# Warmie_Helper_Board_V_9_5_GND_EN_3_3v.net
KiCad netlist of a schematic drawn in EAGLE
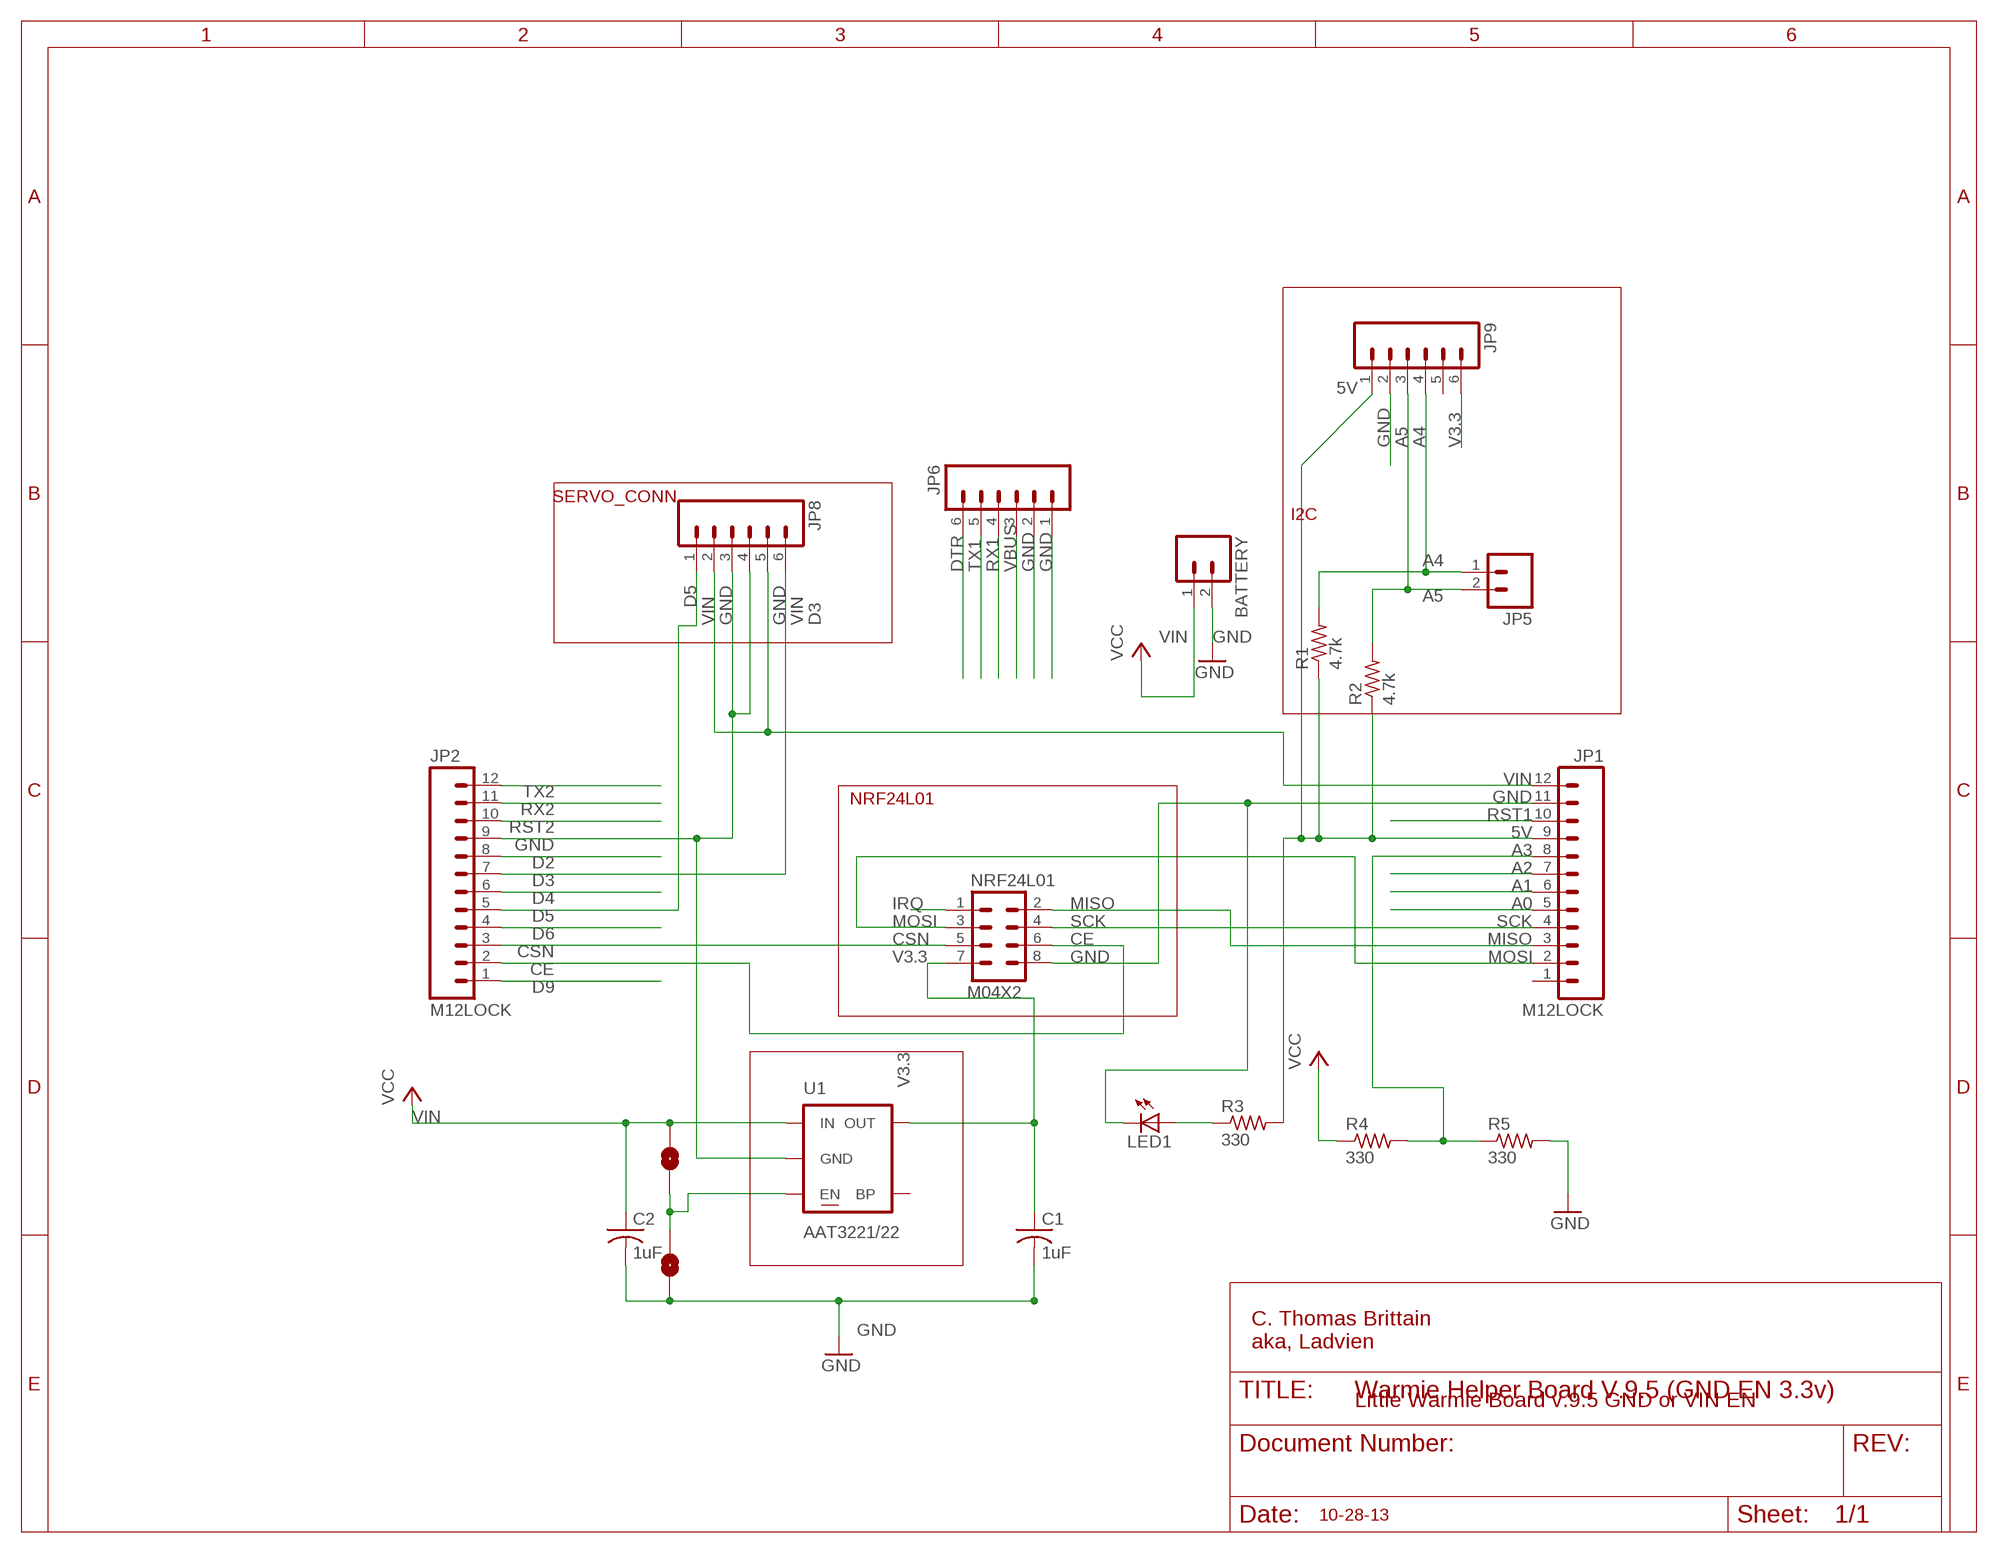
[diagram p0: schematic, sheet 1]

(export (version "E")
  (design (tool "Eeschema 10.0.6"))
  (components
    (comp (ref "BATTERY")
      (value "M02LOCK")
      (footprint "eagle-import:1X02_LOCK")
      (libsource (lib "eagle-import") (part "M02LOCK"))
    )
    (comp (ref "C1")
      (value "1uF")
      (footprint "eagle-import:C0805")
      (libsource (lib "eagle-import") (part "C-USC0805"))
    )
    (comp (ref "C2")
      (value "1uF")
      (footprint "eagle-import:C0805")
      (libsource (lib "eagle-import") (part "C-USC0805"))
    )
    (comp (ref "JP1")
      (value "M12LOCK")
      (footprint "eagle-import:1X12_LOCK")
      (libsource (lib "eagle-import") (part "M12LOCK"))
    )
    (comp (ref "JP2")
      (value "M12LOCK")
      (footprint "eagle-import:1X12_LOCK")
      (libsource (lib "eagle-import") (part "M12LOCK"))
    )
    (comp (ref "JP5")
      (value "M02LOCK")
      (footprint "eagle-import:1X02_LOCK")
      (libsource (lib "eagle-import") (part "M02LOCK"))
    )
    (comp (ref "JP6")
      (value "M06LOCK")
      (footprint "eagle-import:1X06_LOCK")
      (libsource (lib "eagle-import") (part "M06LOCK"))
    )
    (comp (ref "JP8")
      (value "M06LOCK")
      (footprint "eagle-import:1X06_LOCK")
      (libsource (lib "eagle-import") (part "M06LOCK"))
    )
    (comp (ref "JP9")
      (value "M06LOCK")
      (footprint "eagle-import:1X06_LOCK")
      (libsource (lib "eagle-import") (part "M06LOCK"))
    )
    (comp (ref "LED1")
      (value "LEDSML0603")
      (footprint "eagle-import:SML0603")
      (libsource (lib "eagle-import") (part "LEDSML0603"))
    )
    (comp (ref "NRF24L01")
      (value "M04X2")
      (footprint "eagle-import:2X4")
      (libsource (lib "eagle-import") (part "M04X2"))
    )
    (comp (ref "R1")
      (value "4.7k")
      (footprint "eagle-import:M0805")
      (libsource (lib "eagle-import") (part "R-US_M0805"))
    )
    (comp (ref "R2")
      (value "4.7k")
      (footprint "eagle-import:M0805")
      (libsource (lib "eagle-import") (part "R-US_M0805"))
    )
    (comp (ref "R3")
      (value "330")
      (footprint "eagle-import:M0805")
      (libsource (lib "eagle-import") (part "R-US_M0805"))
    )
    (comp (ref "R4")
      (value "330")
      (footprint "eagle-import:M0805")
      (libsource (lib "eagle-import") (part "R-US_M0805"))
    )
    (comp (ref "R5")
      (value "330")
      (footprint "eagle-import:M0805")
      (libsource (lib "eagle-import") (part "R-US_M0805"))
    )
    (comp (ref "SJ1")
      (value "SOLDERJUMPERNO")
      (footprint "eagle-import:SJ_2S-NO")
      (libsource (lib "eagle-import") (part "SOLDERJUMPERNO"))
    )
    (comp (ref "SJ2")
      (value "SOLDERJUMPERNO")
      (footprint "eagle-import:SJ_2S-NO")
      (libsource (lib "eagle-import") (part "SOLDERJUMPERNO"))
    )
    (comp (ref "U1")
      (value "AAT3221/22")
      (footprint "eagle-import:SOT23-5")
      (libsource (lib "eagle-import") (part "V_REG_LDOSMD"))
    )
  )
  (nets
    (net (code "1") (name "/5V") (class "Default")
      (node (ref "JP1") (pin "9") (pinfunction "9_9") (pintype "passive"))
      (node (ref "JP9") (pin "1") (pinfunction "1_1") (pintype "passive"))
      (node (ref "R1") (pin "1") (pinfunction "1_1") (pintype "passive"))
      (node (ref "R2") (pin "1") (pinfunction "1_1") (pintype "passive"))
      (node (ref "R3") (pin "2") (pinfunction "2_2") (pintype "passive"))
    )
    (net (code "2") (name "/A0") (class "Default")
      (node (ref "JP1") (pin "5") (pinfunction "5_5") (pintype "passive"))
    )
    (net (code "3") (name "/A1") (class "Default")
      (node (ref "JP1") (pin "6") (pinfunction "6_6") (pintype "passive"))
    )
    (net (code "4") (name "/A2") (class "Default")
      (node (ref "JP1") (pin "7") (pinfunction "7_7") (pintype "passive"))
    )
    (net (code "5") (name "/A3") (class "Default")
      (node (ref "JP1") (pin "8") (pinfunction "8_8") (pintype "passive"))
      (node (ref "R4") (pin "2") (pinfunction "2_2") (pintype "passive"))
      (node (ref "R5") (pin "1") (pinfunction "1_1") (pintype "passive"))
    )
    (net (code "6") (name "/A4") (class "Default")
      (node (ref "JP5") (pin "1") (pinfunction "1_1") (pintype "passive"))
      (node (ref "JP9") (pin "4") (pinfunction "4_4") (pintype "passive"))
      (node (ref "R1") (pin "2") (pinfunction "2_2") (pintype "passive"))
    )
    (net (code "7") (name "/A5") (class "Default")
      (node (ref "JP5") (pin "2") (pinfunction "2_2") (pintype "passive"))
      (node (ref "JP9") (pin "3") (pinfunction "3_3") (pintype "passive"))
      (node (ref "R2") (pin "2") (pinfunction "2_2") (pintype "passive"))
    )
    (net (code "8") (name "/CE") (class "Default")
      (node (ref "JP2") (pin "2") (pinfunction "2_2") (pintype "passive"))
      (node (ref "NRF24L01") (pin "6") (pinfunction "6_6") (pintype "passive"))
    )
    (net (code "9") (name "/CSN") (class "Default")
      (node (ref "JP2") (pin "3") (pinfunction "3_3") (pintype "passive"))
      (node (ref "NRF24L01") (pin "5") (pinfunction "5_5") (pintype "passive"))
    )
    (net (code "10") (name "/D2") (class "Default")
      (node (ref "JP2") (pin "8") (pinfunction "8_8") (pintype "passive"))
    )
    (net (code "11") (name "/D3") (class "Default")
      (node (ref "JP2") (pin "7") (pinfunction "7_7") (pintype "passive"))
      (node (ref "JP8") (pin "6") (pinfunction "6_6") (pintype "passive"))
    )
    (net (code "12") (name "/D4") (class "Default")
      (node (ref "JP2") (pin "6") (pinfunction "6_6") (pintype "passive"))
    )
    (net (code "13") (name "/D5") (class "Default")
      (node (ref "JP2") (pin "5") (pinfunction "5_5") (pintype "passive"))
      (node (ref "JP8") (pin "1") (pinfunction "1_1") (pintype "passive"))
    )
    (net (code "14") (name "/D6") (class "Default")
      (node (ref "JP2") (pin "4") (pinfunction "4_4") (pintype "passive"))
    )
    (net (code "15") (name "/D9") (class "Default")
      (node (ref "JP2") (pin "1") (pinfunction "1_1") (pintype "passive"))
    )
    (net (code "16") (name "/DTR") (class "Default")
      (node (ref "JP6") (pin "6") (pinfunction "6_6") (pintype "passive"))
    )
    (net (code "17") (name "/IRQ") (class "Default")
      (node (ref "NRF24L01") (pin "1") (pinfunction "1_1") (pintype "passive"))
    )
    (net (code "18") (name "/MISO") (class "Default")
      (node (ref "JP1") (pin "3") (pinfunction "3_3") (pintype "passive"))
      (node (ref "NRF24L01") (pin "2") (pinfunction "2_2") (pintype "passive"))
    )
    (net (code "19") (name "/MOSI") (class "Default")
      (node (ref "JP1") (pin "2") (pinfunction "2_2") (pintype "passive"))
      (node (ref "NRF24L01") (pin "3") (pinfunction "3_3") (pintype "passive"))
    )
    (net (code "20") (name "/RST1") (class "Default")
      (node (ref "JP1") (pin "10") (pinfunction "10_10") (pintype "passive"))
    )
    (net (code "21") (name "/RST2") (class "Default")
      (node (ref "JP2") (pin "10") (pinfunction "10_10") (pintype "passive"))
    )
    (net (code "22") (name "/RX1") (class "Default")
      (node (ref "JP6") (pin "4") (pinfunction "4_4") (pintype "passive"))
    )
    (net (code "23") (name "/RX2") (class "Default")
      (node (ref "JP2") (pin "11") (pinfunction "11_11") (pintype "passive"))
    )
    (net (code "24") (name "/SCK") (class "Default")
      (node (ref "JP1") (pin "4") (pinfunction "4_4") (pintype "passive"))
      (node (ref "NRF24L01") (pin "4") (pinfunction "4_4") (pintype "passive"))
    )
    (net (code "25") (name "/TX1") (class "Default")
      (node (ref "JP6") (pin "5") (pinfunction "5_5") (pintype "passive"))
    )
    (net (code "26") (name "/TX2") (class "Default")
      (node (ref "JP2") (pin "12") (pinfunction "12_12") (pintype "passive"))
    )
    (net (code "27") (name "/V3.3") (class "Default")
      (node (ref "C1") (pin "1") (pinfunction "1_1") (pintype "passive"))
      (node (ref "JP9") (pin "6") (pinfunction "6_6") (pintype "passive"))
      (node (ref "NRF24L01") (pin "7") (pinfunction "7_7") (pintype "passive"))
      (node (ref "U1") (pin "5") (pinfunction "OUT_5") (pintype "passive"))
    )
    (net (code "28") (name "/VBUS") (class "Default")
      (node (ref "JP6") (pin "3") (pinfunction "3_3") (pintype "passive"))
    )
    (net (code "29") (name "GND") (class "Default")
      (node (ref "BATTERY") (pin "2") (pinfunction "2_2") (pintype "passive"))
      (node (ref "C1") (pin "2") (pinfunction "2_2") (pintype "passive"))
      (node (ref "C2") (pin "2") (pinfunction "2_2") (pintype "passive"))
      (node (ref "JP1") (pin "11") (pinfunction "11_11") (pintype "passive"))
      (node (ref "JP2") (pin "9") (pinfunction "9_9") (pintype "passive"))
      (node (ref "JP6") (pin "1") (pinfunction "1_1") (pintype "passive"))
      (node (ref "JP6") (pin "2") (pinfunction "2_2") (pintype "passive"))
      (node (ref "JP8") (pin "3") (pinfunction "3_3") (pintype "passive"))
      (node (ref "JP8") (pin "4") (pinfunction "4_4") (pintype "passive"))
      (node (ref "JP9") (pin "2") (pinfunction "2_2") (pintype "passive"))
      (node (ref "LED1") (pin "C") (pinfunction "C_C") (pintype "passive"))
      (node (ref "NRF24L01") (pin "8") (pinfunction "8_8") (pintype "passive"))
      (node (ref "R5") (pin "2") (pinfunction "2_2") (pintype "passive"))
      (node (ref "SJ2") (pin "1") (pinfunction "1_1") (pintype "passive"))
      (node (ref "U1") (pin "2") (pinfunction "GND_2") (pintype "input"))
    )
    (net (code "30") (name "Net-(LED1-PadA)") (class "Default")
      (node (ref "LED1") (pin "A") (pinfunction "A_A") (pintype "passive"))
      (node (ref "R3") (pin "1") (pinfunction "1_1") (pintype "passive"))
    )
    (net (code "31") (name "Net-(U1-EN)") (class "Default")
      (node (ref "SJ1") (pin "1") (pinfunction "1_1") (pintype "passive"))
      (node (ref "SJ2") (pin "2") (pinfunction "2_2") (pintype "passive"))
      (node (ref "U1") (pin "3") (pinfunction "EN_3") (pintype "input"))
    )
    (net (code "32") (name "VCC") (class "Default")
      (node (ref "BATTERY") (pin "1") (pinfunction "1_1") (pintype "passive"))
      (node (ref "C2") (pin "1") (pinfunction "1_1") (pintype "passive"))
      (node (ref "JP1") (pin "12") (pinfunction "12_12") (pintype "passive"))
      (node (ref "JP8") (pin "2") (pinfunction "2_2") (pintype "passive"))
      (node (ref "JP8") (pin "5") (pinfunction "5_5") (pintype "passive"))
      (node (ref "R4") (pin "1") (pinfunction "1_1") (pintype "passive"))
      (node (ref "SJ1") (pin "2") (pinfunction "2_2") (pintype "passive"))
      (node (ref "U1") (pin "1") (pinfunction "IN_1") (pintype "input"))
    )
    (net (code "33") (name "unconnected-(JP1-Pad1)") (class "Default")
      (node (ref "JP1") (pin "1") (pinfunction "1_1") (pintype "passive"))
    )
    (net (code "34") (name "unconnected-(JP9-Pad5)") (class "Default")
      (node (ref "JP9") (pin "5") (pinfunction "5_5") (pintype "passive"))
    )
    (net (code "35") (name "unconnected-(U1-BP-Pad4)") (class "Default")
      (node (ref "U1") (pin "4") (pinfunction "BP_4") (pintype "input"))
    )
  )
)
